# emonTH_V3_0_0.net
KiCad netlist of a schematic drawn in EAGLE
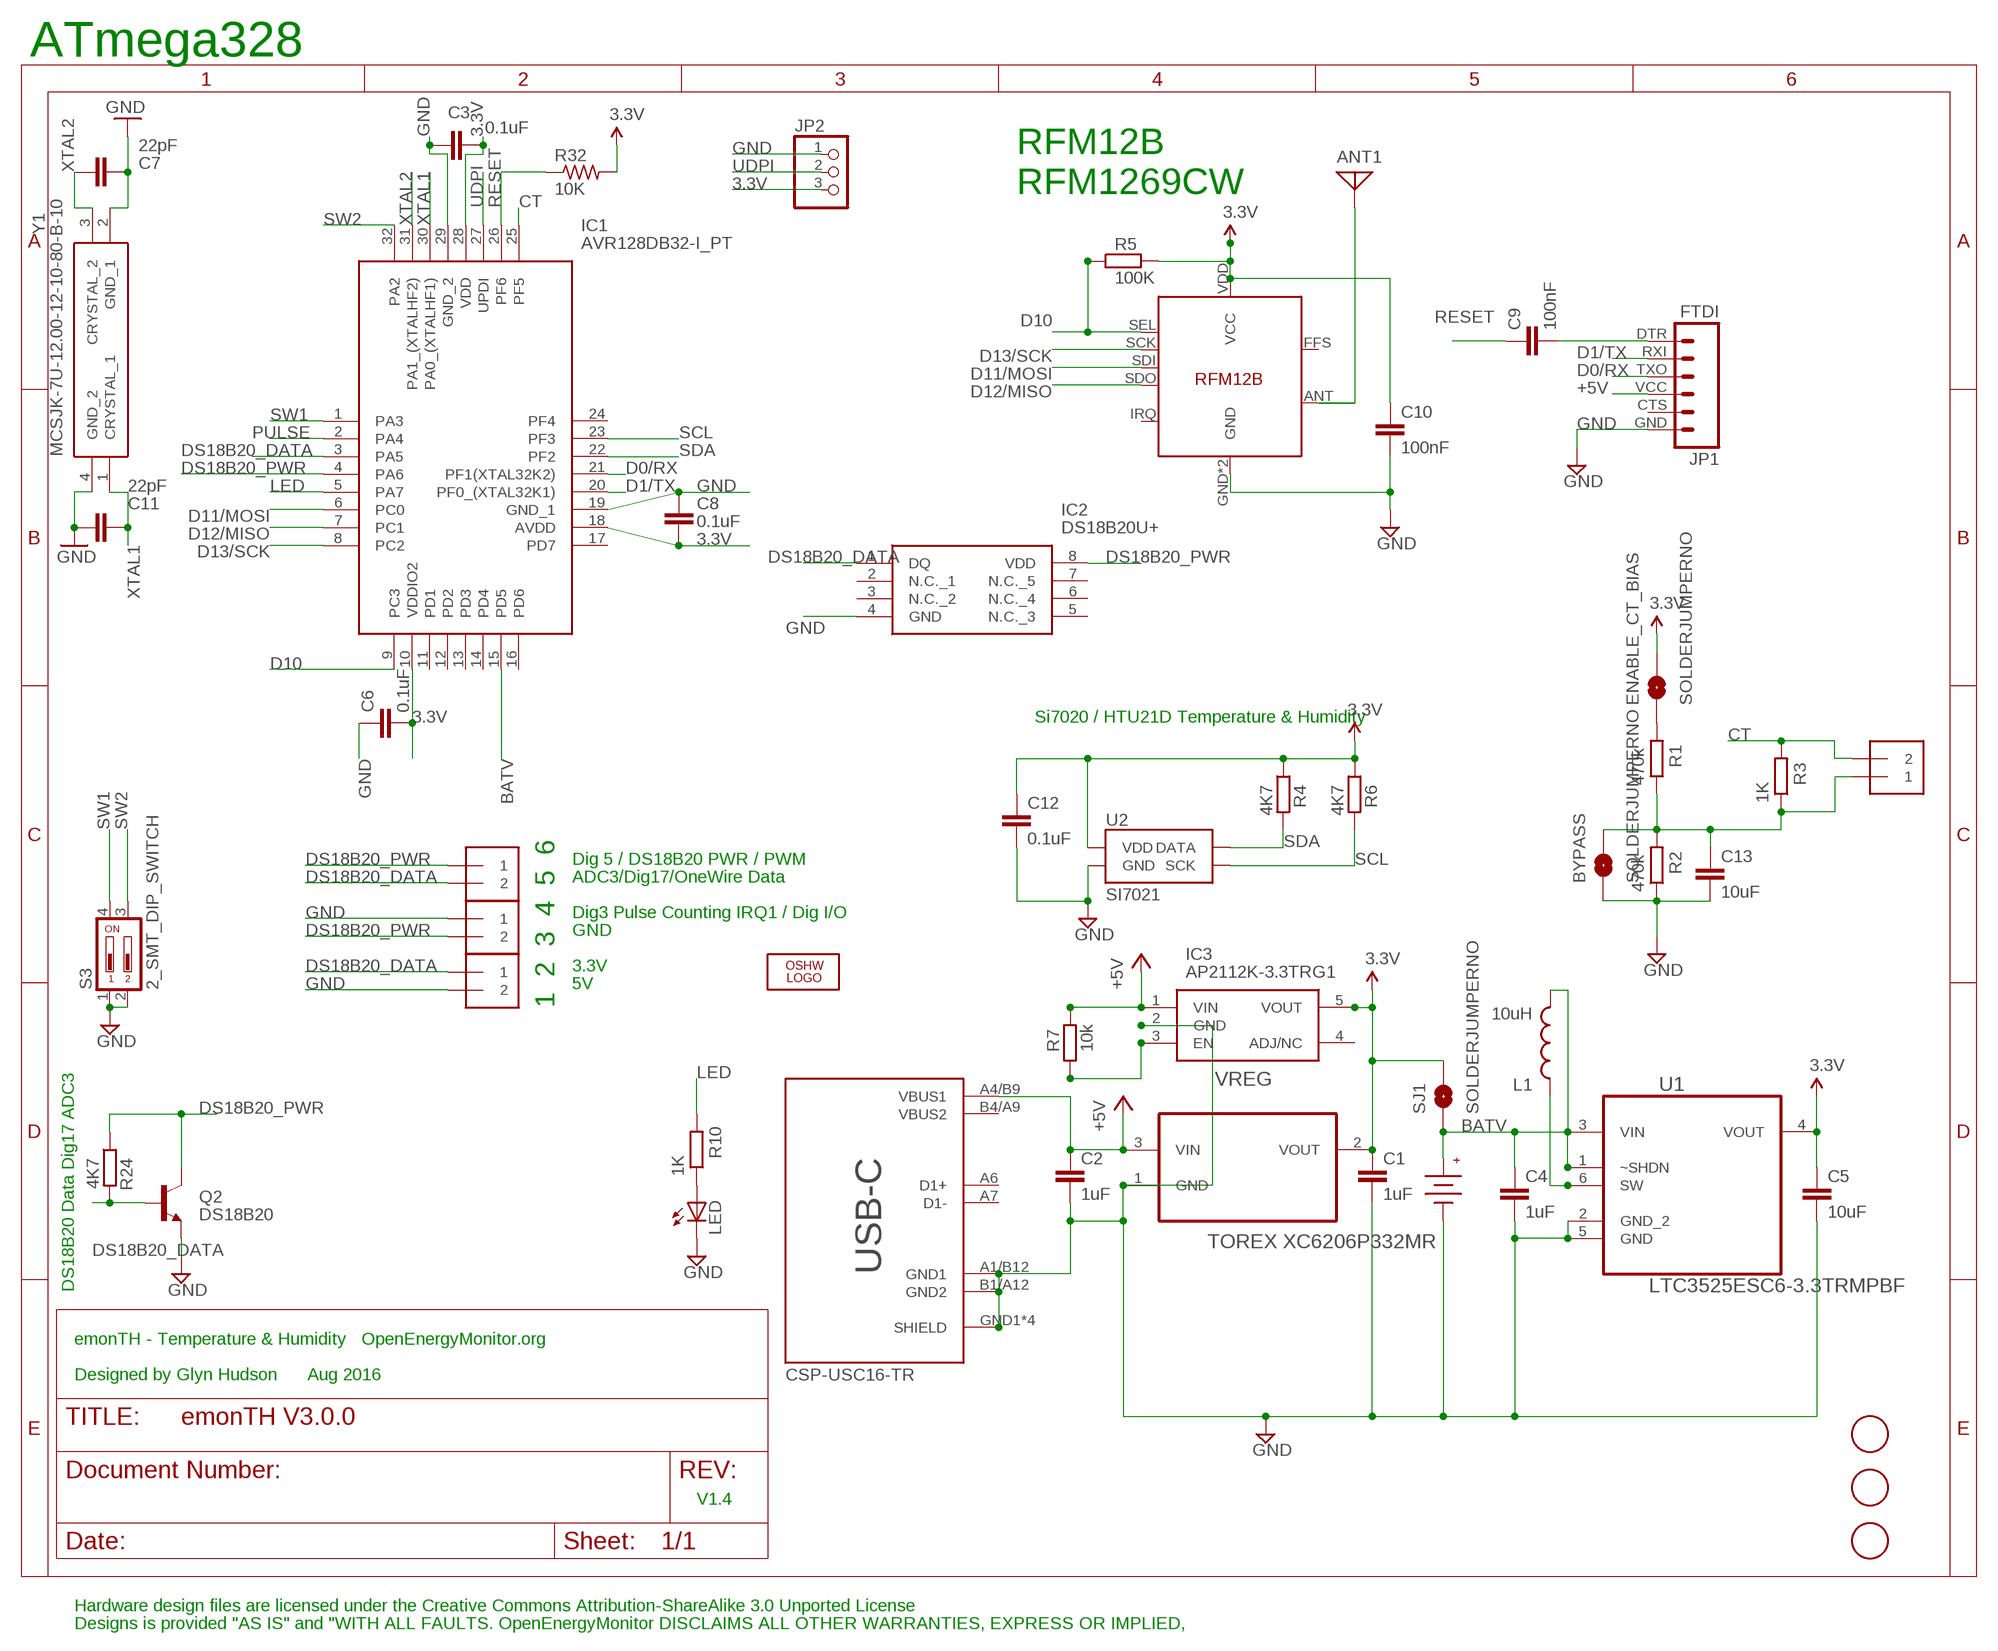
[diagram p0: schematic, sheet 1]

(export (version "E")
  (design (tool "Eeschema 10.0.6"))
  (components
    (comp (ref "ANT1")
      (value "ANTENNA")
      (footprint "eagle-import:PAD-01")
      (libsource (lib "eagle-import") (part "ANTENNA"))
    )
    (comp (ref "BYPASS")
      (value "SOLDERJUMPERNO")
      (footprint "eagle-import:SJ_2S-NO")
      (libsource (lib "eagle-import") (part "SOLDERJUMPERNO"))
    )
    (comp (ref "C1")
      (value "1uF")
      (footprint "eagle-import:C0603")
      (libsource (lib "eagle-import") (part "resistor_C-EUC0603"))
    )
    (comp (ref "C2")
      (value "1uF")
      (footprint "eagle-import:C0603")
      (libsource (lib "eagle-import") (part "resistor_C-EUC0603"))
    )
    (comp (ref "C3")
      (value "0.1uF")
      (footprint "eagle-import:C0603")
      (libsource (lib "eagle-import") (part "C-EUC0603"))
    )
    (comp (ref "C4")
      (value "1uF")
      (footprint "eagle-import:C0603")
      (libsource (lib "eagle-import") (part "resistor_C-EUC0603"))
    )
    (comp (ref "C5")
      (value "10uF")
      (footprint "eagle-import:C0603")
      (libsource (lib "eagle-import") (part "resistor_C-EUC0603"))
    )
    (comp (ref "C6")
      (value "0.1uF")
      (footprint "eagle-import:C0603")
      (libsource (lib "eagle-import") (part "resistor_C-EUC0603"))
    )
    (comp (ref "C7")
      (value "22pF")
      (footprint "eagle-import:C0603")
      (libsource (lib "eagle-import") (part "resistor_C-EUC0603"))
    )
    (comp (ref "C8")
      (value "0.1uF")
      (footprint "eagle-import:C0603")
      (libsource (lib "eagle-import") (part "resistor_C-EUC0603"))
    )
    (comp (ref "C9")
      (value "100nF")
      (footprint "eagle-import:C0603")
      (libsource (lib "eagle-import") (part "C-EUC0603"))
    )
    (comp (ref "C10")
      (value "100nF")
      (footprint "eagle-import:C0603")
      (libsource (lib "eagle-import") (part "C-EUC0603"))
    )
    (comp (ref "C11")
      (value "22pF")
      (footprint "eagle-import:C0603")
      (libsource (lib "eagle-import") (part "resistor_C-EUC0603"))
    )
    (comp (ref "C12")
      (value "0.1uF")
      (footprint "eagle-import:C0603")
      (libsource (lib "eagle-import") (part "resistor_C-EUC0603"))
    )
    (comp (ref "C13")
      (value "10uF")
      (footprint "eagle-import:C0603")
      (libsource (lib "eagle-import") (part "resistor_C-EUC0603"))
    )
    (comp (ref "ENABLE_CT_BIAS")
      (value "SOLDERJUMPERNO")
      (footprint "eagle-import:SJ_2S-NO")
      (libsource (lib "eagle-import") (part "SOLDERJUMPERNO"))
    )
    (comp (ref "IC1")
      (value "AVR128DB32-I_PT")
      (footprint "eagle-import:QFP80P900X900X120-32N")
      (fields
        (field (name "ARROW_PART_NUMBER") "AVR128DB32-I/PT")
        (field (name "MOUSER_PART_NUMBER") "579-AVR128DB32-I/PT")
      )
      (libsource (lib "eagle-import") (part "AVR128DB32-I_PT"))
    )
    (comp (ref "IC2")
      (value "DS18B20U+")
      (footprint "eagle-import:SOP65P490X110-8N")
      (fields (field (name "MOUSER_PART_NUMBER") "700-DS18B20U"))
      (libsource (lib "eagle-import") (part "DS18B20U+"))
    )
    (comp (ref "IC3")
      (value "AP2112K-3.3TRG1")
      (footprint "eagle-import:SOT95P282X130-5N")
      (fields (field (name "MOUSER_PART_NUMBER") "621-AP2112K-3.3TRG1"))
      (libsource (lib "eagle-import") (part "AP2112K-3.3TRG1"))
    )
    (comp (ref "J1")
      (value "1X2-3.5MM")
      (footprint "eagle-import:1X2-3.5MM")
      (libsource (lib "eagle-import") (part "1X2-3.5MM"))
    )
    (comp (ref "J2")
      (value "1X2-3.5MM")
      (footprint "eagle-import:1X2-3.5MM")
      (libsource (lib "eagle-import") (part "1X2-3.5MM"))
    )
    (comp (ref "J3")
      (value "1X2-3.5MM")
      (footprint "eagle-import:1X2-3.5MM")
      (libsource (lib "eagle-import") (part "1X2-3.5MM"))
    )
    (comp (ref "J4")
      (value "1X2-3.5MM")
      (footprint "eagle-import:1X2-3.5MM")
      (libsource (lib "eagle-import") (part "1X2-3.5MM"))
    )
    (comp (ref "JP1")
      (value "FTDI")
      (footprint "eagle-import:FTDI_BASIC")
      (libsource (lib "eagle-import") (part "FTDI_BASICPTH"))
    )
    (comp (ref "JP2")
      (value "PINHD-1X3")
      (footprint "eagle-import:1X03")
      (libsource (lib "eagle-import") (part "PINHD-1X3"))
    )
    (comp (ref "L1")
      (value "10uH")
      (footprint "eagle-import:1210")
      (libsource (lib "eagle-import") (part "INDUCTOR1210"))
    )
    (comp (ref "LED")
      (value "LEDCHIPLED-0603-TTW")
      (footprint "eagle-import:CHIPLED-0603-TTW")
      (libsource (lib "eagle-import") (part "LEDCHIPLED-0603-TTW"))
    )
    (comp (ref "LOGO2")
      (value "OSHW_LOGO_10MILX0200-NT")
      (footprint "eagle-import:OSHW_10X200_NOTEXT")
      (libsource (lib "eagle-import") (part "OSHW_LOGO_10MILX0200-NT"))
    )
    (comp (ref "Q2")
      (value "DS18B20")
      (footprint "eagle-import:TO-92")
      (libsource (lib "eagle-import") (part "TRANSISTOR_NPNTO92"))
    )
    (comp (ref "R1")
      (value "470k")
      (footprint "eagle-import:R0603")
      (libsource (lib "eagle-import") (part "resistor_R-EU_R0603"))
    )
    (comp (ref "R2")
      (value "470k")
      (footprint "eagle-import:R0603")
      (libsource (lib "eagle-import") (part "resistor_R-EU_R0603"))
    )
    (comp (ref "R3")
      (value "1K")
      (footprint "eagle-import:R0603")
      (libsource (lib "eagle-import") (part "resistor_R-EU_R0603"))
    )
    (comp (ref "R4")
      (value "4K7")
      (footprint "eagle-import:R0603")
      (libsource (lib "eagle-import") (part "resistor_R-EU_R0603"))
    )
    (comp (ref "R5")
      (value "100K")
      (footprint "eagle-import:R0603")
      (libsource (lib "eagle-import") (part "R-EU_R0603"))
    )
    (comp (ref "R6")
      (value "4K7")
      (footprint "eagle-import:R0603")
      (libsource (lib "eagle-import") (part "resistor_R-EU_R0603"))
    )
    (comp (ref "R7")
      (value "10k")
      (footprint "eagle-import:R0603")
      (libsource (lib "eagle-import") (part "R-EU_R0603"))
    )
    (comp (ref "R10")
      (value "1K")
      (footprint "eagle-import:R0603")
      (libsource (lib "eagle-import") (part "resistor_R-EU_R0603"))
    )
    (comp (ref "R24")
      (value "4K7")
      (footprint "eagle-import:R0603")
      (libsource (lib "eagle-import") (part "resistor_R-EU_R0603"))
    )
    (comp (ref "R32")
      (value "10K")
      (footprint "eagle-import:R0603")
      (libsource (lib "eagle-import") (part "R-US_R0603"))
    )
    (comp (ref "RFM69CW")
      (value "RFM12B")
      (footprint "eagle-import:RFM12B")
      (libsource (lib "eagle-import") (part "RFM12B"))
    )
    (comp (ref "S3")
      (value "2_SMT_DIP_SWITCH")
      (footprint "eagle-import:DIP_SWITCH_SMT")
      (libsource (lib "eagle-import") (part "2_SMT_DIP_SWITCH"))
    )
    (comp (ref "SJ1")
      (value "SOLDERJUMPERNO")
      (footprint "eagle-import:SJ_2S-NO")
      (libsource (lib "eagle-import") (part "SOLDERJUMPERNO"))
    )
    (comp (ref "U$1")
      (value "FIDUCIAL")
      (footprint "eagle-import:FIDUCIAL_1MM")
      (libsource (lib "eagle-import") (part "FIDUCIAL"))
    )
    (comp (ref "U$3")
      (value "3V")
      (footprint "eagle-import:AAA_PCB_HOLDER")
      (libsource (lib "eagle-import") (part "3X_AAA_BATTERY_HOLDER"))
    )
    (comp (ref "U$6")
      (value "FIDUCIAL")
      (footprint "eagle-import:FIDUCIAL_1MM")
      (libsource (lib "eagle-import") (part "FIDUCIAL"))
    )
    (comp (ref "U$7")
      (value "FIDUCIAL")
      (footprint "eagle-import:FIDUCIAL_1MM")
      (libsource (lib "eagle-import") (part "FIDUCIAL"))
    )
    (comp (ref "U1")
      (value "LTC3525ESC6-3.3TRMPBF")
      (footprint "eagle-import:SOT65P210X100-6N")
      (fields (field (name "MPN") "LTC3525ESC6-3.3#TRMPBF"))
      (libsource (lib "eagle-import") (part "LTC3525ESC6-3.3TRMPBF"))
    )
    (comp (ref "U2")
      (value "SI7021")
      (footprint "eagle-import:SI7021")
      (libsource (lib "eagle-import") (part "SI7021"))
    )
    (comp (ref "USB-C")
      (value "CSP-USC16-TR")
      (footprint "eagle-import:USB-C")
      (libsource (lib "eagle-import") (part "CSP-USC16-TR"))
    )
    (comp (ref "VREG")
      (value "TOREX XC6206P332MR")
      (footprint "eagle-import:SOT95P237X112-3N")
      (fields (field (name "MPN") "MCP1700T-3302E/TT"))
      (libsource (lib "eagle-import") (part "MCP1700T-3302E/TT"))
    )
    (comp (ref "Y1")
      (value "MCSJK-7U-12.00-12-10-80-B-10")
      (footprint "eagle-import:MCSJK7U1200121080B10")
      (libsource (lib "eagle-import") (part "MCSJK-7U-12.00-12-10-80-B-10"))
    )
  )
  (nets
    (net (code "1") (name "+5V") (class "Default")
      (node (ref "C2") (pin "1") (pinfunction "1_1") (pintype "passive"))
      (node (ref "IC3") (pin "1") (pinfunction "VIN_1") (pintype "bidirectional"))
      (node (ref "JP1") (pin "VCC") (pinfunction "4_VCC") (pintype "passive"))
      (node (ref "R7") (pin "2") (pinfunction "2_2") (pintype "passive"))
      (node (ref "USB-C") (pin "A4/B9") (pinfunction "VBUS1_A4/B9") (pintype "passive"))
      (node (ref "VREG") (pin "3") (pinfunction "VIN_3") (pintype "input"))
    )
    (net (code "2") (name "/BATV") (class "Default")
      (node (ref "C4") (pin "1") (pinfunction "1_1") (pintype "passive"))
      (node (ref "IC1") (pin "15") (pinfunction "PD5_15") (pintype "bidirectional"))
      (node (ref "L1") (pin "2") (pinfunction "2_2") (pintype "passive"))
      (node (ref "SJ1") (pin "1") (pinfunction "1_1") (pintype "passive"))
      (node (ref "U$3") (pin "+") (pinfunction "+_+") (pintype "power_in"))
      (node (ref "U1") (pin "1") (pinfunction "~{SHDN}_1") (pintype "input"))
      (node (ref "U1") (pin "3") (pinfunction "VIN_3") (pintype "input"))
    )
    (net (code "3") (name "/CT") (class "Default")
      (node (ref "IC1") (pin "25") (pinfunction "PF5_25") (pintype "bidirectional"))
      (node (ref "J4") (pin "2") (pinfunction "2_2") (pintype "passive"))
      (node (ref "R3") (pin "2") (pinfunction "2_2") (pintype "passive"))
    )
    (net (code "4") (name "/D0{slash}RX") (class "Default")
      (node (ref "IC1") (pin "21") (pinfunction "PF1(XTAL32K2)_21") (pintype "bidirectional"))
      (node (ref "JP1") (pin "TXO") (pinfunction "3_TXO") (pintype "passive"))
    )
    (net (code "5") (name "/D1{slash}TX") (class "Default")
      (node (ref "IC1") (pin "20") (pinfunction "PF0_(XTAL32K1)_20") (pintype "bidirectional"))
      (node (ref "JP1") (pin "RXI") (pinfunction "2_RXI") (pintype "passive"))
    )
    (net (code "6") (name "/D10") (class "Default")
      (node (ref "IC1") (pin "9") (pinfunction "PC3_9") (pintype "bidirectional"))
      (node (ref "R5") (pin "1") (pinfunction "1_1") (pintype "passive"))
      (node (ref "RFM69CW") (pin "SEL") (pinfunction "SEL_SEL") (pintype "input"))
    )
    (net (code "7") (name "/D11{slash}MOSI") (class "Default")
      (node (ref "IC1") (pin "6") (pinfunction "PC0_6") (pintype "bidirectional"))
      (node (ref "RFM69CW") (pin "SDI") (pinfunction "SDI_SDI") (pintype "input"))
    )
    (net (code "8") (name "/D12{slash}MISO") (class "Default")
      (node (ref "IC1") (pin "7") (pinfunction "PC1_7") (pintype "bidirectional"))
      (node (ref "RFM69CW") (pin "SDO") (pinfunction "SDO_SDO") (pintype "output"))
    )
    (net (code "9") (name "/D13{slash}SCK") (class "Default")
      (node (ref "IC1") (pin "8") (pinfunction "PC2_8") (pintype "bidirectional"))
      (node (ref "RFM69CW") (pin "SCK") (pinfunction "SCK_SCK") (pintype "input"))
    )
    (net (code "10") (name "/DS18B20_DATA") (class "Default")
      (node (ref "IC1") (pin "3") (pinfunction "PA5_3") (pintype "bidirectional"))
      (node (ref "IC2") (pin "1") (pinfunction "DQ_1") (pintype "bidirectional"))
      (node (ref "J1") (pin "2") (pinfunction "2_2") (pintype "passive"))
      (node (ref "J3") (pin "1") (pinfunction "1_1") (pintype "passive"))
      (node (ref "Q2") (pin "2") (pinfunction "B_2") (pintype "passive"))
      (node (ref "R24") (pin "2") (pinfunction "2_2") (pintype "passive"))
    )
    (net (code "11") (name "/DS18B20_PWR") (class "Default")
      (node (ref "IC1") (pin "4") (pinfunction "PA6_4") (pintype "bidirectional"))
      (node (ref "IC2") (pin "8") (pinfunction "VDD_8") (pintype "bidirectional"))
      (node (ref "J1") (pin "1") (pinfunction "1_1") (pintype "passive"))
      (node (ref "J2") (pin "2") (pinfunction "2_2") (pintype "passive"))
      (node (ref "Q2") (pin "3") (pinfunction "C_3") (pintype "passive"))
      (node (ref "R24") (pin "1") (pinfunction "1_1") (pintype "passive"))
    )
    (net (code "12") (name "/LED") (class "Default")
      (node (ref "IC1") (pin "5") (pinfunction "PA7_5") (pintype "bidirectional"))
      (node (ref "R10") (pin "2") (pinfunction "2_2") (pintype "passive"))
    )
    (net (code "13") (name "/PULSE") (class "Default")
      (node (ref "IC1") (pin "2") (pinfunction "PA4_2") (pintype "bidirectional"))
    )
    (net (code "14") (name "/RESET") (class "Default")
      (node (ref "C9") (pin "1") (pinfunction "1_1") (pintype "passive"))
      (node (ref "IC1") (pin "26") (pinfunction "PF6_26") (pintype "bidirectional"))
      (node (ref "R32") (pin "1") (pinfunction "1_1") (pintype "passive"))
    )
    (net (code "15") (name "/SCL") (class "Default")
      (node (ref "IC1") (pin "23") (pinfunction "PF3_23") (pintype "bidirectional"))
      (node (ref "R6") (pin "2") (pinfunction "2_2") (pintype "passive"))
      (node (ref "U2") (pin "SCK") (pinfunction "SCK_SCK") (pintype "input"))
    )
    (net (code "16") (name "/SDA") (class "Default")
      (node (ref "IC1") (pin "22") (pinfunction "PF2_22") (pintype "bidirectional"))
      (node (ref "R4") (pin "2") (pinfunction "2_2") (pintype "passive"))
      (node (ref "U2") (pin "DATA") (pinfunction "DATA_DATA") (pintype "bidirectional"))
    )
    (net (code "17") (name "/SW1") (class "Default")
      (node (ref "IC1") (pin "1") (pinfunction "PA3_1") (pintype "bidirectional"))
      (node (ref "S3") (pin "4") (pinfunction "4_4") (pintype "passive"))
    )
    (net (code "18") (name "/SW2") (class "Default")
      (node (ref "IC1") (pin "32") (pinfunction "PA2_32") (pintype "bidirectional"))
      (node (ref "S3") (pin "3") (pinfunction "3_3") (pintype "passive"))
    )
    (net (code "19") (name "/UDPI") (class "Default")
      (node (ref "IC1") (pin "27") (pinfunction "UPDI_27") (pintype "bidirectional"))
      (node (ref "JP2") (pin "2") (pinfunction "2_2") (pintype "passive"))
    )
    (net (code "20") (name "/XTAL1") (class "Default")
      (node (ref "C11") (pin "1") (pinfunction "1_1") (pintype "passive"))
      (node (ref "IC1") (pin "30") (pinfunction "PA0_(XTALHF1)_30") (pintype "bidirectional"))
      (node (ref "Y1") (pin "1") (pinfunction "CRYSTAL_1_1") (pintype "bidirectional"))
    )
    (net (code "21") (name "/XTAL2") (class "Default")
      (node (ref "C7") (pin "2") (pinfunction "2_2") (pintype "passive"))
      (node (ref "IC1") (pin "31") (pinfunction "PA1_(XTALHF2)_31") (pintype "bidirectional"))
      (node (ref "Y1") (pin "3") (pinfunction "CRYSTAL_2_3") (pintype "bidirectional"))
    )
    (net (code "22") (name "3.3V") (class "Default")
      (node (ref "C1") (pin "1") (pinfunction "1_1") (pintype "passive"))
      (node (ref "C10") (pin "1") (pinfunction "1_1") (pintype "passive"))
      (node (ref "C12") (pin "1") (pinfunction "1_1") (pintype "passive"))
      (node (ref "C3") (pin "1") (pinfunction "1_1") (pintype "passive"))
      (node (ref "C5") (pin "1") (pinfunction "1_1") (pintype "passive"))
      (node (ref "C6") (pin "2") (pinfunction "2_2") (pintype "passive"))
      (node (ref "C8") (pin "2") (pinfunction "2_2") (pintype "passive"))
      (node (ref "ENABLE_CT_BIAS") (pin "2") (pinfunction "2_2") (pintype "passive"))
      (node (ref "IC1") (pin "10") (pinfunction "VDDIO2_10") (pintype "bidirectional"))
      (node (ref "IC1") (pin "18") (pinfunction "AVDD_18") (pintype "bidirectional"))
      (node (ref "IC1") (pin "28") (pinfunction "VDD_28") (pintype "bidirectional"))
      (node (ref "IC3") (pin "5") (pinfunction "VOUT_5") (pintype "bidirectional"))
      (node (ref "JP2") (pin "3") (pinfunction "3_3") (pintype "passive"))
      (node (ref "R32") (pin "2") (pinfunction "2_2") (pintype "passive"))
      (node (ref "R4") (pin "1") (pinfunction "1_1") (pintype "passive"))
      (node (ref "R5") (pin "2") (pinfunction "2_2") (pintype "passive"))
      (node (ref "R6") (pin "1") (pinfunction "1_1") (pintype "passive"))
      (node (ref "RFM69CW") (pin "VDD") (pinfunction "VCC_VDD") (pintype "power_in"))
      (node (ref "SJ1") (pin "2") (pinfunction "2_2") (pintype "passive"))
      (node (ref "U1") (pin "4") (pinfunction "VOUT_4") (pintype "output"))
      (node (ref "U2") (pin "VDD") (pinfunction "VDD_VDD") (pintype "power_in"))
      (node (ref "VREG") (pin "2") (pinfunction "VOUT_2") (pintype "output"))
    )
    (net (code "23") (name "GND") (class "Default")
      (node (ref "BYPASS") (pin "1") (pinfunction "1_1") (pintype "passive"))
      (node (ref "C1") (pin "2") (pinfunction "2_2") (pintype "passive"))
      (node (ref "C10") (pin "2") (pinfunction "2_2") (pintype "passive"))
      (node (ref "C11") (pin "2") (pinfunction "2_2") (pintype "passive"))
      (node (ref "C12") (pin "2") (pinfunction "2_2") (pintype "passive"))
      (node (ref "C13") (pin "2") (pinfunction "2_2") (pintype "passive"))
      (node (ref "C2") (pin "2") (pinfunction "2_2") (pintype "passive"))
      (node (ref "C3") (pin "2") (pinfunction "2_2") (pintype "passive"))
      (node (ref "C4") (pin "2") (pinfunction "2_2") (pintype "passive"))
      (node (ref "C5") (pin "2") (pinfunction "2_2") (pintype "passive"))
      (node (ref "C6") (pin "1") (pinfunction "1_1") (pintype "passive"))
      (node (ref "C7") (pin "1") (pinfunction "1_1") (pintype "passive"))
      (node (ref "C8") (pin "1") (pinfunction "1_1") (pintype "passive"))
      (node (ref "IC1") (pin "19") (pinfunction "GND_1_19") (pintype "bidirectional"))
      (node (ref "IC1") (pin "29") (pinfunction "GND_2_29") (pintype "bidirectional"))
      (node (ref "IC2") (pin "4") (pinfunction "GND_4") (pintype "bidirectional"))
      (node (ref "IC3") (pin "2") (pinfunction "GND_2") (pintype "bidirectional"))
      (node (ref "J2") (pin "1") (pinfunction "1_1") (pintype "passive"))
      (node (ref "J3") (pin "2") (pinfunction "2_2") (pintype "passive"))
      (node (ref "JP1") (pin "GND") (pinfunction "6_GND") (pintype "passive"))
      (node (ref "JP2") (pin "1") (pinfunction "1_1") (pintype "passive"))
      (node (ref "LED") (pin "C") (pinfunction "C_C") (pintype "passive"))
      (node (ref "Q2") (pin "1") (pinfunction "E_1") (pintype "passive"))
      (node (ref "R2") (pin "1") (pinfunction "1_1") (pintype "passive"))
      (node (ref "RFM69CW") (pin "GND") (pinfunction "GND_GND") (pintype "power_in"))
      (node (ref "RFM69CW") (pin "P$12") (pinfunction "GND_P$12") (pintype "power_in"))
      (node (ref "S3") (pin "1") (pinfunction "1_1") (pintype "passive"))
      (node (ref "S3") (pin "2") (pinfunction "2_2") (pintype "passive"))
      (node (ref "U$3") (pin "-") (pinfunction "-_-") (pintype "power_in"))
      (node (ref "U1") (pin "2") (pinfunction "GND_2_2") (pintype "passive"))
      (node (ref "U1") (pin "5") (pinfunction "GND_5") (pintype "passive"))
      (node (ref "U2") (pin "GND") (pinfunction "GND_GND") (pintype "power_in"))
      (node (ref "USB-C") (pin "A1/B12") (pinfunction "GND1_A1/B12") (pintype "passive"))
      (node (ref "USB-C") (pin "B1/A12") (pinfunction "GND2_B1/A12") (pintype "passive"))
      (node (ref "USB-C") (pin "GND1") (pinfunction "SHIELD_GND1") (pintype "bidirectional"))
      (node (ref "USB-C") (pin "GND2") (pinfunction "SHIELD_GND2") (pintype "bidirectional"))
      (node (ref "USB-C") (pin "GND3") (pinfunction "SHIELD_GND3") (pintype "bidirectional"))
      (node (ref "USB-C") (pin "GND4") (pinfunction "SHIELD_GND4") (pintype "bidirectional"))
      (node (ref "VREG") (pin "1") (pinfunction "GND_1") (pintype "passive"))
      (node (ref "Y1") (pin "2") (pinfunction "GND_1_2") (pintype "bidirectional"))
      (node (ref "Y1") (pin "4") (pinfunction "GND_2_4") (pintype "bidirectional"))
    )
    (net (code "24") (name "Net-(ANT1-Pad1)") (class "Default")
      (node (ref "ANT1") (pin "1") (pinfunction "1_1") (pintype "output"))
      (node (ref "RFM69CW") (pin "ANT") (pinfunction "ANT_ANT") (pintype "passive"))
    )
    (net (code "25") (name "Net-(BYPASS-Pad2)") (class "Default")
      (node (ref "BYPASS") (pin "2") (pinfunction "2_2") (pintype "passive"))
      (node (ref "C13") (pin "1") (pinfunction "1_1") (pintype "passive"))
      (node (ref "J4") (pin "1") (pinfunction "1_1") (pintype "passive"))
      (node (ref "R1") (pin "1") (pinfunction "1_1") (pintype "passive"))
      (node (ref "R2") (pin "2") (pinfunction "2_2") (pintype "passive"))
      (node (ref "R3") (pin "1") (pinfunction "1_1") (pintype "passive"))
    )
    (net (code "26") (name "Net-(ENABLE_CT_BIAS-Pad1)") (class "Default")
      (node (ref "ENABLE_CT_BIAS") (pin "1") (pinfunction "1_1") (pintype "passive"))
      (node (ref "R1") (pin "2") (pinfunction "2_2") (pintype "passive"))
    )
    (net (code "27") (name "Net-(IC3-EN)") (class "Default")
      (node (ref "IC3") (pin "3") (pinfunction "EN_3") (pintype "bidirectional"))
      (node (ref "R7") (pin "1") (pinfunction "1_1") (pintype "passive"))
    )
    (net (code "28") (name "Net-(JP1-1)") (class "Default")
      (node (ref "C9") (pin "2") (pinfunction "2_2") (pintype "passive"))
      (node (ref "JP1") (pin "DTR") (pinfunction "1_DTR") (pintype "passive"))
    )
    (net (code "29") (name "Net-(LED-PadA)") (class "Default")
      (node (ref "LED") (pin "A") (pinfunction "A_A") (pintype "passive"))
      (node (ref "R10") (pin "1") (pinfunction "1_1") (pintype "passive"))
    )
    (net (code "30") (name "Net-(U1-SW)") (class "Default")
      (node (ref "L1") (pin "1") (pinfunction "1_1") (pintype "passive"))
      (node (ref "U1") (pin "6") (pinfunction "SW_6") (pintype "input"))
    )
    (net (code "31") (name "unconnected-(IC1-PD1-Pad11)") (class "Default")
      (node (ref "IC1") (pin "11") (pinfunction "PD1_11") (pintype "bidirectional"))
    )
    (net (code "32") (name "unconnected-(IC1-PD2-Pad12)") (class "Default")
      (node (ref "IC1") (pin "12") (pinfunction "PD2_12") (pintype "bidirectional"))
    )
    (net (code "33") (name "unconnected-(IC1-PD3-Pad13)") (class "Default")
      (node (ref "IC1") (pin "13") (pinfunction "PD3_13") (pintype "bidirectional"))
    )
    (net (code "34") (name "unconnected-(IC1-PD4-Pad14)") (class "Default")
      (node (ref "IC1") (pin "14") (pinfunction "PD4_14") (pintype "bidirectional"))
    )
    (net (code "35") (name "unconnected-(IC1-PD6-Pad16)") (class "Default")
      (node (ref "IC1") (pin "16") (pinfunction "PD6_16") (pintype "bidirectional"))
    )
    (net (code "36") (name "unconnected-(IC1-PD7-Pad17)") (class "Default")
      (node (ref "IC1") (pin "17") (pinfunction "PD7_17") (pintype "bidirectional"))
    )
    (net (code "37") (name "unconnected-(IC1-PF4-Pad24)") (class "Default")
      (node (ref "IC1") (pin "24") (pinfunction "PF4_24") (pintype "bidirectional"))
    )
    (net (code "38") (name "unconnected-(IC2-N.C._1-Pad2)") (class "Default")
      (node (ref "IC2") (pin "2") (pinfunction "N.C._1_2") (pintype "bidirectional"))
    )
    (net (code "39") (name "unconnected-(IC2-N.C._2-Pad3)") (class "Default")
      (node (ref "IC2") (pin "3") (pinfunction "N.C._2_3") (pintype "bidirectional"))
    )
    (net (code "40") (name "unconnected-(IC2-N.C._3-Pad5)") (class "Default")
      (node (ref "IC2") (pin "5") (pinfunction "N.C._3_5") (pintype "bidirectional"))
    )
    (net (code "41") (name "unconnected-(IC2-N.C._4-Pad6)") (class "Default")
      (node (ref "IC2") (pin "6") (pinfunction "N.C._4_6") (pintype "bidirectional"))
    )
    (net (code "42") (name "unconnected-(IC2-N.C._5-Pad7)") (class "Default")
      (node (ref "IC2") (pin "7") (pinfunction "N.C._5_7") (pintype "bidirectional"))
    )
    (net (code "43") (name "unconnected-(IC3-ADJ{slash}NC-Pad4)") (class "Default")
      (node (ref "IC3") (pin "4") (pinfunction "ADJ/NC_4") (pintype "bidirectional"))
    )
    (net (code "44") (name "unconnected-(JP1-5-PadCTS)") (class "Default")
      (node (ref "JP1") (pin "CTS") (pinfunction "5_CTS") (pintype "passive"))
    )
    (net (code "45") (name "unconnected-(RFM69CW-PadFFS)") (class "Default")
      (node (ref "RFM69CW") (pin "FFS") (pinfunction "FFS_FFS") (pintype "bidirectional"))
    )
    (net (code "46") (name "unconnected-(RFM69CW-PadIRQ)") (class "Default")
      (node (ref "RFM69CW") (pin "IRQ") (pinfunction "IRQ_IRQ") (pintype "open_collector"))
    )
    (net (code "47") (name "unconnected-(USB-C-D1+-PadA6)") (class "Default")
      (node (ref "USB-C") (pin "A6") (pinfunction "D1+_A6") (pintype "passive"))
    )
    (net (code "48") (name "unconnected-(USB-C-D1--PadA7)") (class "Default")
      (node (ref "USB-C") (pin "A7") (pinfunction "D1-_A7") (pintype "passive"))
    )
    (net (code "49") (name "unconnected-(USB-C-VBUS2-PadB4{slash}A9)") (class "Default")
      (node (ref "USB-C") (pin "B4/A9") (pinfunction "VBUS2_B4/A9") (pintype "passive"))
    )
  )
)
